# 1-Schematic_BIG_MODULE.net
KiCad netlist of a schematic drawn in EasyEDA
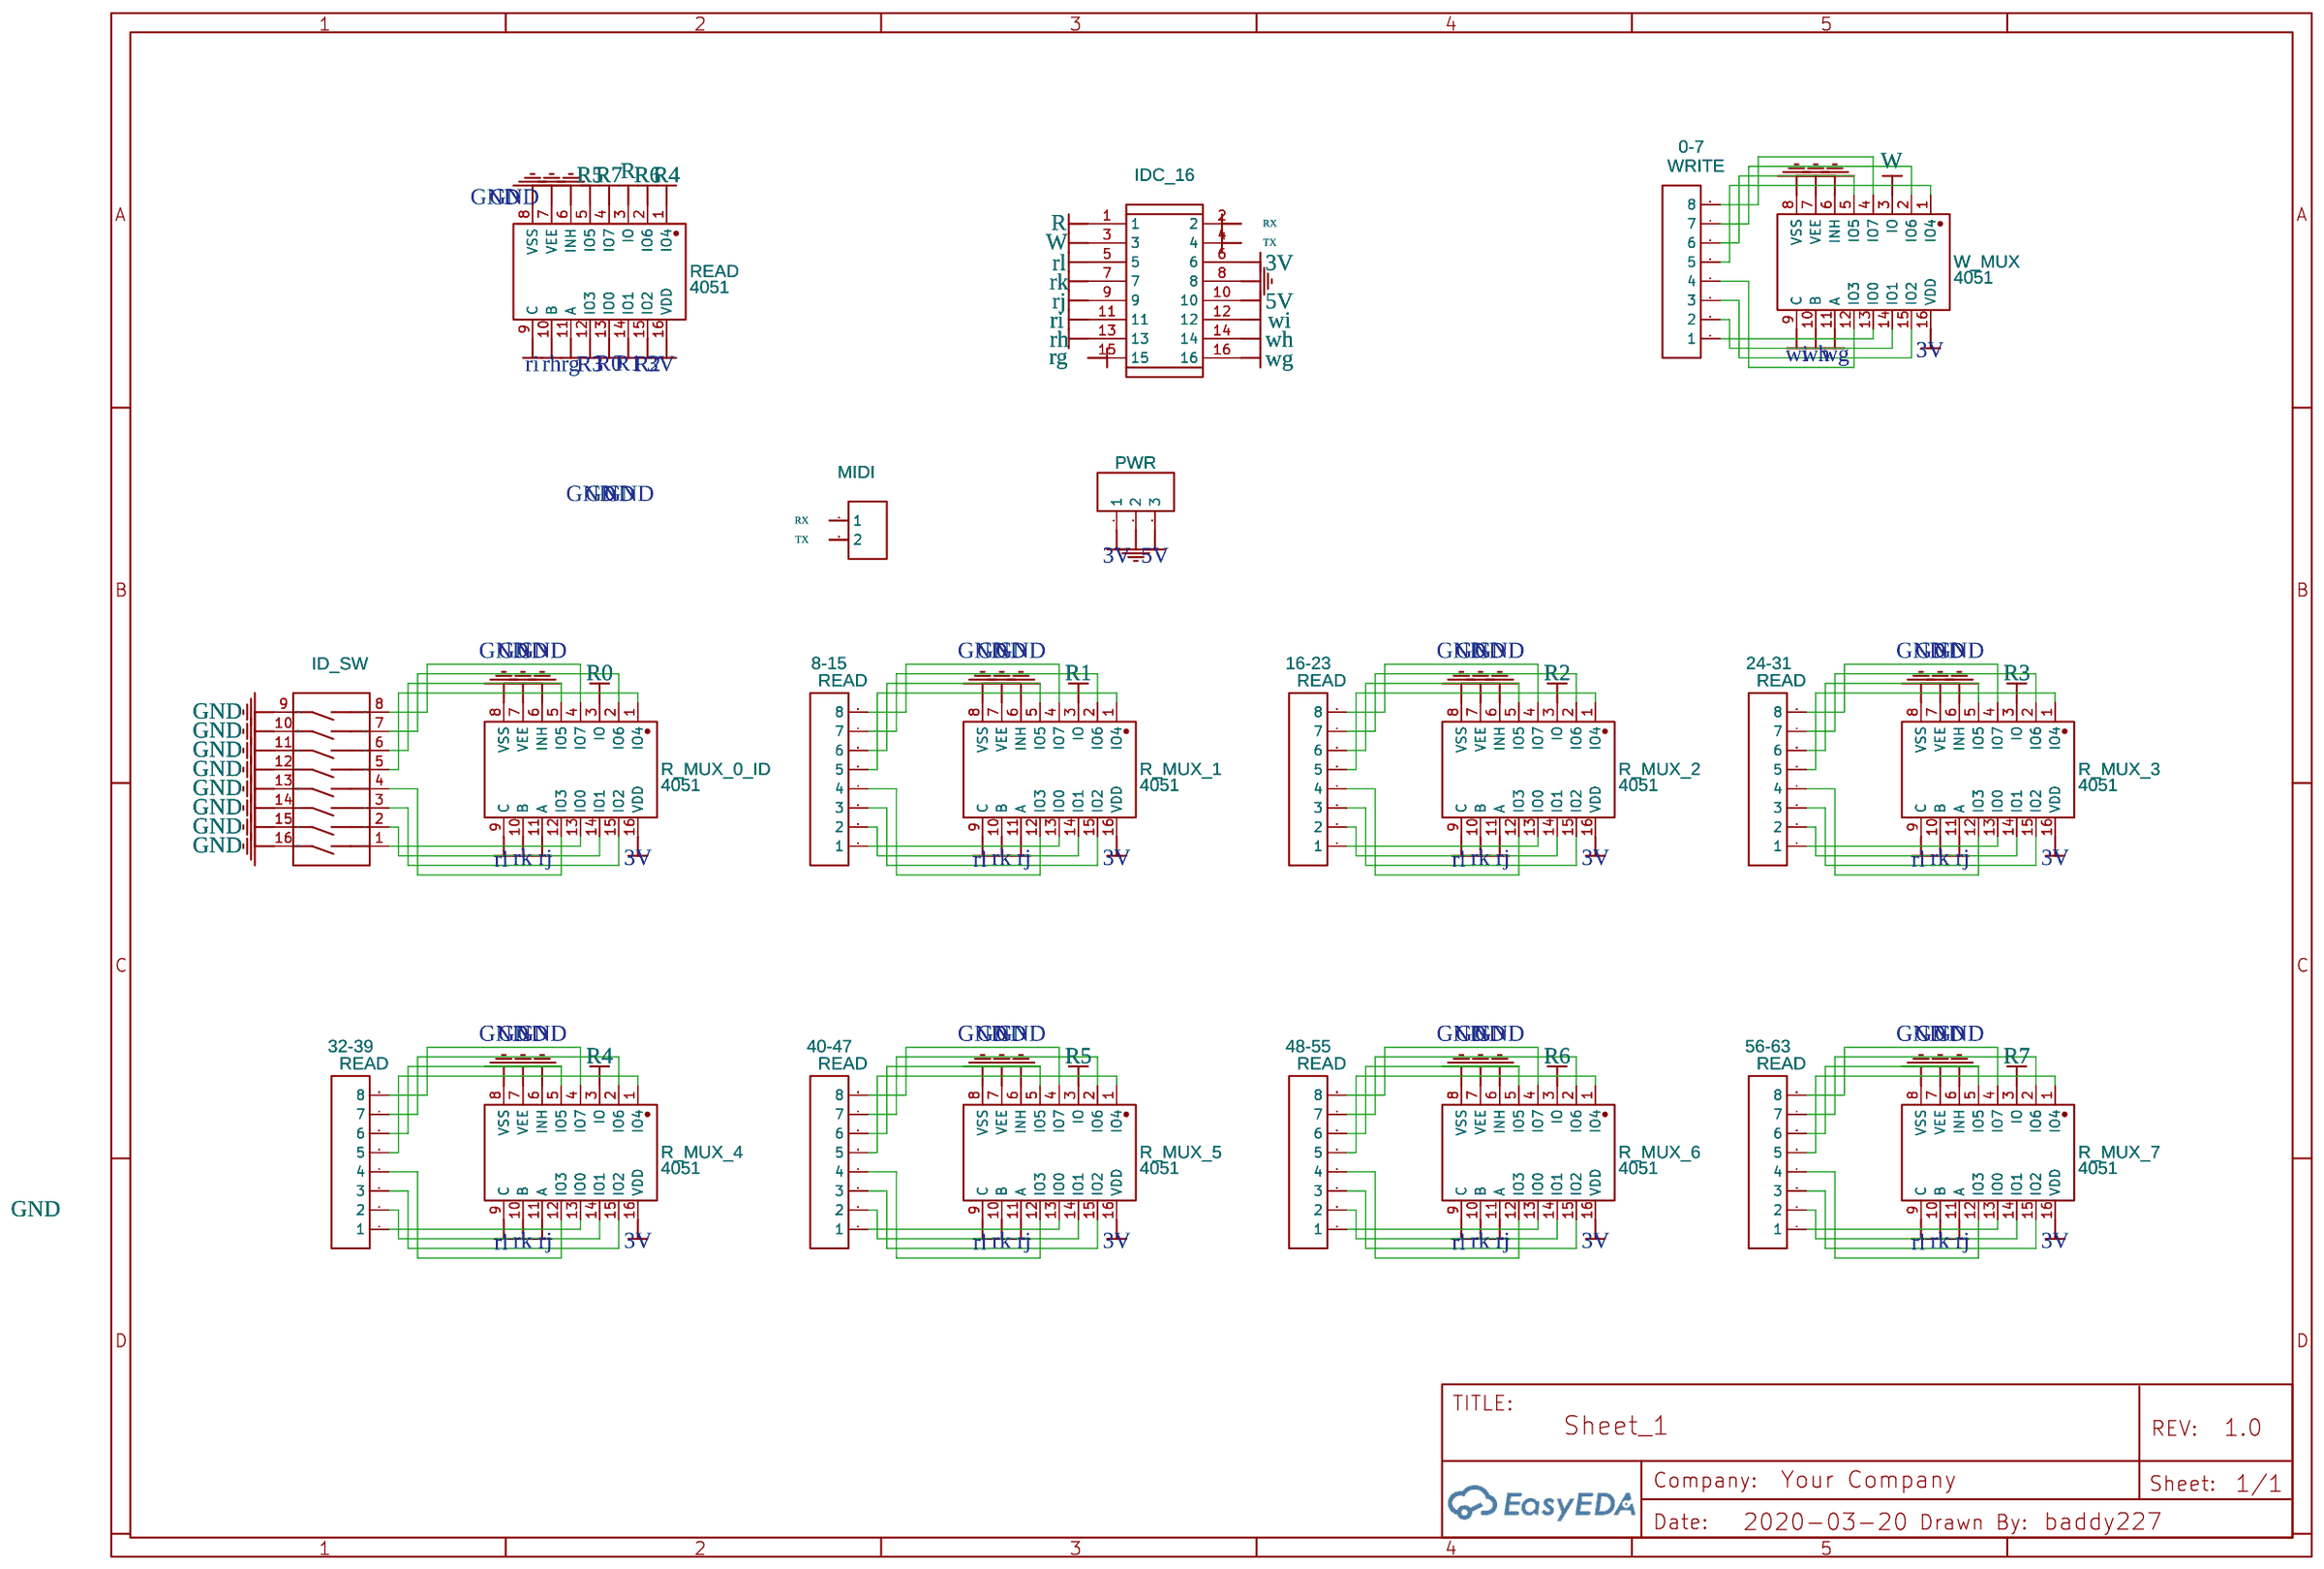
[diagram p0: schematic sheet]

(export (version "E")
  (design (tool "Eeschema 10.0.6"))
  (components
    (comp (ref "8-15")
      (value "READ")
      (fields
        (field (name "BOM_Manufacturer Part") "Female headerHDR1X8-2.54")
        (field (name "BOM_Supplier Part") "C27438")
      )
      (libsource (lib "") (part "Header-Female-2.54_1x8_7"))
    )
    (comp (ref "16-23")
      (value "READ")
      (fields
        (field (name "BOM_Manufacturer Part") "Female headerHDR1X8-2.54")
        (field (name "BOM_Supplier Part") "C27438")
      )
      (libsource (lib "") (part "Header-Female-2.54_1x8_4"))
    )
    (comp (ref "24-31")
      (value "READ")
      (fields
        (field (name "BOM_Manufacturer Part") "Female headerHDR1X8-2.54")
        (field (name "BOM_Supplier Part") "C27438")
      )
      (libsource (lib "") (part "Header-Female-2.54_1x8_3"))
    )
    (comp (ref "32-39")
      (value "READ")
      (fields
        (field (name "BOM_Manufacturer Part") "Female headerHDR1X8-2.54")
        (field (name "BOM_Supplier Part") "C27438")
      )
      (libsource (lib "") (part "Header-Female-2.54_1x8_6"))
    )
    (comp (ref "40-47")
      (value "READ")
      (fields
        (field (name "BOM_Manufacturer Part") "Female headerHDR1X8-2.54")
        (field (name "BOM_Supplier Part") "C27438")
      )
      (libsource (lib "") (part "Header-Female-2.54_1x8"))
    )
    (comp (ref "48-55")
      (value "READ")
      (fields
        (field (name "BOM_Manufacturer Part") "Female headerHDR1X8-2.54")
        (field (name "BOM_Supplier Part") "C27438")
      )
      (libsource (lib "") (part "Header-Female-2.54_1x8_1"))
    )
    (comp (ref "56-63")
      (value "READ")
      (fields
        (field (name "BOM_Manufacturer Part") "Female headerHDR1X8-2.54")
        (field (name "BOM_Supplier Part") "C27438")
      )
      (libsource (lib "") (part "Header-Female-2.54_1x8_2"))
    )
    (comp (ref "IDC_16")
      (value "IDC Box 2X8 2.54MM")
      (fields (field (name "BOM_Supplier Part") "C9142"))
      (libsource (lib "") (part "IDC Box 2X8 2.54MM"))
    )
    (comp (ref "ID_SW")
      (value "DIP switchEI-08")
      (fields (field (name "BOM_Supplier Part") "C90019"))
      (libsource (lib "") (part "DIP switchEI-08"))
    )
    (comp (ref "MIDI")
      (value "HDR-M-2.54_1x2")
      (fields (field (name "BOM_Supplier Part") "C124375"))
      (libsource (lib "") (part "HDR-M-2.54_1x2"))
    )
    (comp (ref "PWR")
      (value "Header-Male-2.54_1x3")
      (fields
        (field (name "BOM_Manufacturer Part") "Header2.54mm 1*3P")
        (field (name "BOM_Supplier Part") "C49257")
      )
      (libsource (lib "") (part "Header-Male-2.54_1x3"))
    )
    (comp (ref "READ")
      (value "4051")
      (fields (field (name "BOM_Manufacturer Part") "CD4051BE") (field (name "BOM_Supplier Part") "C5200"))
      (libsource (lib "") (part "CD4051BE_3"))
    )
    (comp (ref "R_MUX_0_ID")
      (value "4051")
      (fields (field (name "BOM_Manufacturer Part") "CD4051BE") (field (name "BOM_Supplier Part") "C5200"))
      (libsource (lib "") (part "CD4051BE_1"))
    )
    (comp (ref "R_MUX_1")
      (value "4051")
      (fields (field (name "BOM_Manufacturer Part") "CD4051BE") (field (name "BOM_Supplier Part") "C5200"))
      (libsource (lib "") (part "CD4051BE_2"))
    )
    (comp (ref "R_MUX_2")
      (value "4051")
      (fields (field (name "BOM_Manufacturer Part") "CD4051BE") (field (name "BOM_Supplier Part") "C5200"))
      (libsource (lib "") (part "CD4051BE_2"))
    )
    (comp (ref "R_MUX_3")
      (value "4051")
      (fields (field (name "BOM_Manufacturer Part") "CD4051BE") (field (name "BOM_Supplier Part") "C5200"))
      (libsource (lib "") (part "CD4051BE_2"))
    )
    (comp (ref "R_MUX_4")
      (value "4051")
      (fields (field (name "BOM_Manufacturer Part") "CD4051BE") (field (name "BOM_Supplier Part") "C5200"))
      (libsource (lib "") (part "CD4051BE_2"))
    )
    (comp (ref "R_MUX_5")
      (value "4051")
      (fields (field (name "BOM_Manufacturer Part") "CD4051BE") (field (name "BOM_Supplier Part") "C5200"))
      (libsource (lib "") (part "CD4051BE_2"))
    )
    (comp (ref "R_MUX_6")
      (value "4051")
      (fields (field (name "BOM_Manufacturer Part") "CD4051BE") (field (name "BOM_Supplier Part") "C5200"))
      (libsource (lib "") (part "CD4051BE_2"))
    )
    (comp (ref "R_MUX_7")
      (value "4051")
      (fields (field (name "BOM_Manufacturer Part") "CD4051BE") (field (name "BOM_Supplier Part") "C5200"))
      (libsource (lib "") (part "CD4051BE_2"))
    )
    (comp (ref "WRITE")
      (value "0-7")
      (fields
        (field (name "BOM_Manufacturer Part") "Female headerHDR1X8-2.54")
        (field (name "BOM_Supplier Part") "C27438")
      )
      (libsource (lib "") (part "Header-Female-2.54_1x8_5"))
    )
    (comp (ref "W_MUX")
      (value "4051")
      (fields (field (name "BOM_Manufacturer Part") "CD4051BE") (field (name "BOM_Supplier Part") "C5200"))
      (libsource (lib "") (part "CD4051BE"))
    )
  )
  (nets
    (net (code "1") (name "3V") (class "Default")
      (node (ref "IDC_16") (pin "6") (pinfunction "6_6") (pintype "unspecified"))
      (node (ref "PWR") (pin "1") (pinfunction "1_1") (pintype "input"))
      (node (ref "READ") (pin "16") (pinfunction "VDD_16") (pintype "unspecified"))
      (node (ref "R_MUX_0_ID") (pin "16") (pinfunction "VDD_16") (pintype "unspecified"))
      (node (ref "R_MUX_1") (pin "16") (pinfunction "VDD_16") (pintype "unspecified"))
      (node (ref "R_MUX_2") (pin "16") (pinfunction "VDD_16") (pintype "unspecified"))
      (node (ref "R_MUX_3") (pin "16") (pinfunction "VDD_16") (pintype "unspecified"))
      (node (ref "R_MUX_4") (pin "16") (pinfunction "VDD_16") (pintype "unspecified"))
      (node (ref "R_MUX_5") (pin "16") (pinfunction "VDD_16") (pintype "unspecified"))
      (node (ref "R_MUX_6") (pin "16") (pinfunction "VDD_16") (pintype "unspecified"))
      (node (ref "R_MUX_7") (pin "16") (pinfunction "VDD_16") (pintype "unspecified"))
      (node (ref "W_MUX") (pin "16") (pinfunction "VDD_16") (pintype "unspecified"))
    )
    (net (code "2") (name "5V") (class "Default")
      (node (ref "IDC_16") (pin "10") (pinfunction "10_10") (pintype "unspecified"))
      (node (ref "PWR") (pin "3") (pinfunction "3_3") (pintype "input"))
    )
    (net (code "3") (name "GND") (class "Default")
      (node (ref "IDC_16") (pin "8") (pinfunction "8_8") (pintype "unspecified"))
      (node (ref "ID_SW") (pin "10") (pinfunction "10_10") (pintype "unspecified"))
      (node (ref "ID_SW") (pin "11") (pinfunction "11_11") (pintype "unspecified"))
      (node (ref "ID_SW") (pin "12") (pinfunction "12_12") (pintype "unspecified"))
      (node (ref "ID_SW") (pin "13") (pinfunction "13_13") (pintype "unspecified"))
      (node (ref "ID_SW") (pin "14") (pinfunction "14_14") (pintype "unspecified"))
      (node (ref "ID_SW") (pin "15") (pinfunction "15_15") (pintype "unspecified"))
      (node (ref "ID_SW") (pin "16") (pinfunction "16_16") (pintype "unspecified"))
      (node (ref "ID_SW") (pin "9") (pinfunction "9_9") (pintype "unspecified"))
      (node (ref "PWR") (pin "2") (pinfunction "2_2") (pintype "input"))
      (node (ref "READ") (pin "6") (pinfunction "INH_6") (pintype "unspecified"))
      (node (ref "READ") (pin "7") (pinfunction "VEE_7") (pintype "unspecified"))
      (node (ref "READ") (pin "8") (pinfunction "VSS_8") (pintype "unspecified"))
      (node (ref "R_MUX_0_ID") (pin "6") (pinfunction "INH_6") (pintype "unspecified"))
      (node (ref "R_MUX_0_ID") (pin "7") (pinfunction "VEE_7") (pintype "unspecified"))
      (node (ref "R_MUX_0_ID") (pin "8") (pinfunction "VSS_8") (pintype "unspecified"))
      (node (ref "R_MUX_1") (pin "6") (pinfunction "INH_6") (pintype "unspecified"))
      (node (ref "R_MUX_1") (pin "7") (pinfunction "VEE_7") (pintype "unspecified"))
      (node (ref "R_MUX_1") (pin "8") (pinfunction "VSS_8") (pintype "unspecified"))
      (node (ref "R_MUX_2") (pin "6") (pinfunction "INH_6") (pintype "unspecified"))
      (node (ref "R_MUX_2") (pin "7") (pinfunction "VEE_7") (pintype "unspecified"))
      (node (ref "R_MUX_2") (pin "8") (pinfunction "VSS_8") (pintype "unspecified"))
      (node (ref "R_MUX_3") (pin "6") (pinfunction "INH_6") (pintype "unspecified"))
      (node (ref "R_MUX_3") (pin "7") (pinfunction "VEE_7") (pintype "unspecified"))
      (node (ref "R_MUX_3") (pin "8") (pinfunction "VSS_8") (pintype "unspecified"))
      (node (ref "R_MUX_4") (pin "6") (pinfunction "INH_6") (pintype "unspecified"))
      (node (ref "R_MUX_4") (pin "7") (pinfunction "VEE_7") (pintype "unspecified"))
      (node (ref "R_MUX_4") (pin "8") (pinfunction "VSS_8") (pintype "unspecified"))
      (node (ref "R_MUX_5") (pin "6") (pinfunction "INH_6") (pintype "unspecified"))
      (node (ref "R_MUX_5") (pin "7") (pinfunction "VEE_7") (pintype "unspecified"))
      (node (ref "R_MUX_5") (pin "8") (pinfunction "VSS_8") (pintype "unspecified"))
      (node (ref "R_MUX_6") (pin "6") (pinfunction "INH_6") (pintype "unspecified"))
      (node (ref "R_MUX_6") (pin "7") (pinfunction "VEE_7") (pintype "unspecified"))
      (node (ref "R_MUX_6") (pin "8") (pinfunction "VSS_8") (pintype "unspecified"))
      (node (ref "R_MUX_7") (pin "6") (pinfunction "INH_6") (pintype "unspecified"))
      (node (ref "R_MUX_7") (pin "7") (pinfunction "VEE_7") (pintype "unspecified"))
      (node (ref "R_MUX_7") (pin "8") (pinfunction "VSS_8") (pintype "unspecified"))
      (node (ref "W_MUX") (pin "6") (pinfunction "INH_6") (pintype "unspecified"))
      (node (ref "W_MUX") (pin "7") (pinfunction "VEE_7") (pintype "unspecified"))
      (node (ref "W_MUX") (pin "8") (pinfunction "VSS_8") (pintype "unspecified"))
    )
    (net (code "4") (name "Net-(R_MUX_0_ID-IO0)") (class "Default")
      (node (ref "ID_SW") (pin "1") (pinfunction "1_1") (pintype "unspecified"))
      (node (ref "R_MUX_0_ID") (pin "13") (pinfunction "IO0_13") (pintype "unspecified"))
    )
    (net (code "5") (name "Net-(R_MUX_0_ID-IO1)") (class "Default")
      (node (ref "ID_SW") (pin "2") (pinfunction "2_2") (pintype "unspecified"))
      (node (ref "R_MUX_0_ID") (pin "14") (pinfunction "IO1_14") (pintype "unspecified"))
    )
    (net (code "6") (name "Net-(R_MUX_0_ID-IO2)") (class "Default")
      (node (ref "ID_SW") (pin "3") (pinfunction "3_3") (pintype "unspecified"))
      (node (ref "R_MUX_0_ID") (pin "15") (pinfunction "IO2_15") (pintype "unspecified"))
    )
    (net (code "7") (name "Net-(R_MUX_0_ID-IO3)") (class "Default")
      (node (ref "ID_SW") (pin "4") (pinfunction "4_4") (pintype "unspecified"))
      (node (ref "R_MUX_0_ID") (pin "12") (pinfunction "IO3_12") (pintype "unspecified"))
    )
    (net (code "8") (name "Net-(R_MUX_0_ID-IO4)") (class "Default")
      (node (ref "ID_SW") (pin "5") (pinfunction "5_5") (pintype "unspecified"))
      (node (ref "R_MUX_0_ID") (pin "1") (pinfunction "IO4_1") (pintype "unspecified"))
    )
    (net (code "9") (name "Net-(R_MUX_0_ID-IO5)") (class "Default")
      (node (ref "ID_SW") (pin "6") (pinfunction "6_6") (pintype "unspecified"))
      (node (ref "R_MUX_0_ID") (pin "5") (pinfunction "IO5_5") (pintype "unspecified"))
    )
    (net (code "10") (name "Net-(R_MUX_0_ID-IO6)") (class "Default")
      (node (ref "ID_SW") (pin "7") (pinfunction "7_7") (pintype "unspecified"))
      (node (ref "R_MUX_0_ID") (pin "2") (pinfunction "IO6_2") (pintype "unspecified"))
    )
    (net (code "11") (name "Net-(R_MUX_0_ID-IO7)") (class "Default")
      (node (ref "ID_SW") (pin "8") (pinfunction "8_8") (pintype "unspecified"))
      (node (ref "R_MUX_0_ID") (pin "4") (pinfunction "IO7_4") (pintype "unspecified"))
    )
    (net (code "12") (name "Net-(R_MUX_1-IO0)") (class "Default")
      (node (ref "8-15") (pin "1") (pinfunction "1_1") (pintype "input"))
      (node (ref "R_MUX_1") (pin "13") (pinfunction "IO0_13") (pintype "unspecified"))
    )
    (net (code "13") (name "Net-(R_MUX_1-IO1)") (class "Default")
      (node (ref "8-15") (pin "2") (pinfunction "2_2") (pintype "input"))
      (node (ref "R_MUX_1") (pin "14") (pinfunction "IO1_14") (pintype "unspecified"))
    )
    (net (code "14") (name "Net-(R_MUX_1-IO2)") (class "Default")
      (node (ref "8-15") (pin "3") (pinfunction "3_3") (pintype "input"))
      (node (ref "R_MUX_1") (pin "15") (pinfunction "IO2_15") (pintype "unspecified"))
    )
    (net (code "15") (name "Net-(R_MUX_1-IO3)") (class "Default")
      (node (ref "8-15") (pin "4") (pinfunction "4_4") (pintype "input"))
      (node (ref "R_MUX_1") (pin "12") (pinfunction "IO3_12") (pintype "unspecified"))
    )
    (net (code "16") (name "Net-(R_MUX_1-IO4)") (class "Default")
      (node (ref "8-15") (pin "5") (pinfunction "5_5") (pintype "input"))
      (node (ref "R_MUX_1") (pin "1") (pinfunction "IO4_1") (pintype "unspecified"))
    )
    (net (code "17") (name "Net-(R_MUX_1-IO5)") (class "Default")
      (node (ref "8-15") (pin "6") (pinfunction "6_6") (pintype "input"))
      (node (ref "R_MUX_1") (pin "5") (pinfunction "IO5_5") (pintype "unspecified"))
    )
    (net (code "18") (name "Net-(R_MUX_1-IO6)") (class "Default")
      (node (ref "8-15") (pin "7") (pinfunction "7_7") (pintype "input"))
      (node (ref "R_MUX_1") (pin "2") (pinfunction "IO6_2") (pintype "unspecified"))
    )
    (net (code "19") (name "Net-(R_MUX_1-IO7)") (class "Default")
      (node (ref "8-15") (pin "8") (pinfunction "8_8") (pintype "input"))
      (node (ref "R_MUX_1") (pin "4") (pinfunction "IO7_4") (pintype "unspecified"))
    )
    (net (code "20") (name "Net-(R_MUX_2-IO0)") (class "Default")
      (node (ref "16-23") (pin "1") (pinfunction "1_1") (pintype "input"))
      (node (ref "R_MUX_2") (pin "13") (pinfunction "IO0_13") (pintype "unspecified"))
    )
    (net (code "21") (name "Net-(R_MUX_2-IO1)") (class "Default")
      (node (ref "16-23") (pin "2") (pinfunction "2_2") (pintype "input"))
      (node (ref "R_MUX_2") (pin "14") (pinfunction "IO1_14") (pintype "unspecified"))
    )
    (net (code "22") (name "Net-(R_MUX_2-IO2)") (class "Default")
      (node (ref "16-23") (pin "3") (pinfunction "3_3") (pintype "input"))
      (node (ref "R_MUX_2") (pin "15") (pinfunction "IO2_15") (pintype "unspecified"))
    )
    (net (code "23") (name "Net-(R_MUX_2-IO3)") (class "Default")
      (node (ref "16-23") (pin "4") (pinfunction "4_4") (pintype "input"))
      (node (ref "R_MUX_2") (pin "12") (pinfunction "IO3_12") (pintype "unspecified"))
    )
    (net (code "24") (name "Net-(R_MUX_2-IO4)") (class "Default")
      (node (ref "16-23") (pin "5") (pinfunction "5_5") (pintype "input"))
      (node (ref "R_MUX_2") (pin "1") (pinfunction "IO4_1") (pintype "unspecified"))
    )
    (net (code "25") (name "Net-(R_MUX_2-IO5)") (class "Default")
      (node (ref "16-23") (pin "6") (pinfunction "6_6") (pintype "input"))
      (node (ref "R_MUX_2") (pin "5") (pinfunction "IO5_5") (pintype "unspecified"))
    )
    (net (code "26") (name "Net-(R_MUX_2-IO6)") (class "Default")
      (node (ref "16-23") (pin "7") (pinfunction "7_7") (pintype "input"))
      (node (ref "R_MUX_2") (pin "2") (pinfunction "IO6_2") (pintype "unspecified"))
    )
    (net (code "27") (name "Net-(R_MUX_2-IO7)") (class "Default")
      (node (ref "16-23") (pin "8") (pinfunction "8_8") (pintype "input"))
      (node (ref "R_MUX_2") (pin "4") (pinfunction "IO7_4") (pintype "unspecified"))
    )
    (net (code "28") (name "Net-(R_MUX_3-IO0)") (class "Default")
      (node (ref "24-31") (pin "1") (pinfunction "1_1") (pintype "input"))
      (node (ref "R_MUX_3") (pin "13") (pinfunction "IO0_13") (pintype "unspecified"))
    )
    (net (code "29") (name "Net-(R_MUX_3-IO1)") (class "Default")
      (node (ref "24-31") (pin "2") (pinfunction "2_2") (pintype "input"))
      (node (ref "R_MUX_3") (pin "14") (pinfunction "IO1_14") (pintype "unspecified"))
    )
    (net (code "30") (name "Net-(R_MUX_3-IO2)") (class "Default")
      (node (ref "24-31") (pin "3") (pinfunction "3_3") (pintype "input"))
      (node (ref "R_MUX_3") (pin "15") (pinfunction "IO2_15") (pintype "unspecified"))
    )
    (net (code "31") (name "Net-(R_MUX_3-IO3)") (class "Default")
      (node (ref "24-31") (pin "4") (pinfunction "4_4") (pintype "input"))
      (node (ref "R_MUX_3") (pin "12") (pinfunction "IO3_12") (pintype "unspecified"))
    )
    (net (code "32") (name "Net-(R_MUX_3-IO4)") (class "Default")
      (node (ref "24-31") (pin "5") (pinfunction "5_5") (pintype "input"))
      (node (ref "R_MUX_3") (pin "1") (pinfunction "IO4_1") (pintype "unspecified"))
    )
    (net (code "33") (name "Net-(R_MUX_3-IO5)") (class "Default")
      (node (ref "24-31") (pin "6") (pinfunction "6_6") (pintype "input"))
      (node (ref "R_MUX_3") (pin "5") (pinfunction "IO5_5") (pintype "unspecified"))
    )
    (net (code "34") (name "Net-(R_MUX_3-IO6)") (class "Default")
      (node (ref "24-31") (pin "7") (pinfunction "7_7") (pintype "input"))
      (node (ref "R_MUX_3") (pin "2") (pinfunction "IO6_2") (pintype "unspecified"))
    )
    (net (code "35") (name "Net-(R_MUX_3-IO7)") (class "Default")
      (node (ref "24-31") (pin "8") (pinfunction "8_8") (pintype "input"))
      (node (ref "R_MUX_3") (pin "4") (pinfunction "IO7_4") (pintype "unspecified"))
    )
    (net (code "36") (name "Net-(R_MUX_4-IO0)") (class "Default")
      (node (ref "32-39") (pin "1") (pinfunction "1_1") (pintype "input"))
      (node (ref "R_MUX_4") (pin "13") (pinfunction "IO0_13") (pintype "unspecified"))
    )
    (net (code "37") (name "Net-(R_MUX_4-IO1)") (class "Default")
      (node (ref "32-39") (pin "2") (pinfunction "2_2") (pintype "input"))
      (node (ref "R_MUX_4") (pin "14") (pinfunction "IO1_14") (pintype "unspecified"))
    )
    (net (code "38") (name "Net-(R_MUX_4-IO2)") (class "Default")
      (node (ref "32-39") (pin "3") (pinfunction "3_3") (pintype "input"))
      (node (ref "R_MUX_4") (pin "15") (pinfunction "IO2_15") (pintype "unspecified"))
    )
    (net (code "39") (name "Net-(R_MUX_4-IO3)") (class "Default")
      (node (ref "32-39") (pin "4") (pinfunction "4_4") (pintype "input"))
      (node (ref "R_MUX_4") (pin "12") (pinfunction "IO3_12") (pintype "unspecified"))
    )
    (net (code "40") (name "Net-(R_MUX_4-IO4)") (class "Default")
      (node (ref "32-39") (pin "5") (pinfunction "5_5") (pintype "input"))
      (node (ref "R_MUX_4") (pin "1") (pinfunction "IO4_1") (pintype "unspecified"))
    )
    (net (code "41") (name "Net-(R_MUX_4-IO5)") (class "Default")
      (node (ref "32-39") (pin "6") (pinfunction "6_6") (pintype "input"))
      (node (ref "R_MUX_4") (pin "5") (pinfunction "IO5_5") (pintype "unspecified"))
    )
    (net (code "42") (name "Net-(R_MUX_4-IO6)") (class "Default")
      (node (ref "32-39") (pin "7") (pinfunction "7_7") (pintype "input"))
      (node (ref "R_MUX_4") (pin "2") (pinfunction "IO6_2") (pintype "unspecified"))
    )
    (net (code "43") (name "Net-(R_MUX_4-IO7)") (class "Default")
      (node (ref "32-39") (pin "8") (pinfunction "8_8") (pintype "input"))
      (node (ref "R_MUX_4") (pin "4") (pinfunction "IO7_4") (pintype "unspecified"))
    )
    (net (code "44") (name "Net-(R_MUX_5-IO0)") (class "Default")
      (node (ref "40-47") (pin "1") (pinfunction "1_1") (pintype "input"))
      (node (ref "R_MUX_5") (pin "13") (pinfunction "IO0_13") (pintype "unspecified"))
    )
    (net (code "45") (name "Net-(R_MUX_5-IO1)") (class "Default")
      (node (ref "40-47") (pin "2") (pinfunction "2_2") (pintype "input"))
      (node (ref "R_MUX_5") (pin "14") (pinfunction "IO1_14") (pintype "unspecified"))
    )
    (net (code "46") (name "Net-(R_MUX_5-IO2)") (class "Default")
      (node (ref "40-47") (pin "3") (pinfunction "3_3") (pintype "input"))
      (node (ref "R_MUX_5") (pin "15") (pinfunction "IO2_15") (pintype "unspecified"))
    )
    (net (code "47") (name "Net-(R_MUX_5-IO3)") (class "Default")
      (node (ref "40-47") (pin "4") (pinfunction "4_4") (pintype "input"))
      (node (ref "R_MUX_5") (pin "12") (pinfunction "IO3_12") (pintype "unspecified"))
    )
    (net (code "48") (name "Net-(R_MUX_5-IO4)") (class "Default")
      (node (ref "40-47") (pin "5") (pinfunction "5_5") (pintype "input"))
      (node (ref "R_MUX_5") (pin "1") (pinfunction "IO4_1") (pintype "unspecified"))
    )
    (net (code "49") (name "Net-(R_MUX_5-IO5)") (class "Default")
      (node (ref "40-47") (pin "6") (pinfunction "6_6") (pintype "input"))
      (node (ref "R_MUX_5") (pin "5") (pinfunction "IO5_5") (pintype "unspecified"))
    )
    (net (code "50") (name "Net-(R_MUX_5-IO6)") (class "Default")
      (node (ref "40-47") (pin "7") (pinfunction "7_7") (pintype "input"))
      (node (ref "R_MUX_5") (pin "2") (pinfunction "IO6_2") (pintype "unspecified"))
    )
    (net (code "51") (name "Net-(R_MUX_5-IO7)") (class "Default")
      (node (ref "40-47") (pin "8") (pinfunction "8_8") (pintype "input"))
      (node (ref "R_MUX_5") (pin "4") (pinfunction "IO7_4") (pintype "unspecified"))
    )
    (net (code "52") (name "Net-(R_MUX_6-IO0)") (class "Default")
      (node (ref "48-55") (pin "1") (pinfunction "1_1") (pintype "input"))
      (node (ref "R_MUX_6") (pin "13") (pinfunction "IO0_13") (pintype "unspecified"))
    )
    (net (code "53") (name "Net-(R_MUX_6-IO1)") (class "Default")
      (node (ref "48-55") (pin "2") (pinfunction "2_2") (pintype "input"))
      (node (ref "R_MUX_6") (pin "14") (pinfunction "IO1_14") (pintype "unspecified"))
    )
    (net (code "54") (name "Net-(R_MUX_6-IO2)") (class "Default")
      (node (ref "48-55") (pin "3") (pinfunction "3_3") (pintype "input"))
      (node (ref "R_MUX_6") (pin "15") (pinfunction "IO2_15") (pintype "unspecified"))
    )
    (net (code "55") (name "Net-(R_MUX_6-IO3)") (class "Default")
      (node (ref "48-55") (pin "4") (pinfunction "4_4") (pintype "input"))
      (node (ref "R_MUX_6") (pin "12") (pinfunction "IO3_12") (pintype "unspecified"))
    )
    (net (code "56") (name "Net-(R_MUX_6-IO4)") (class "Default")
      (node (ref "48-55") (pin "5") (pinfunction "5_5") (pintype "input"))
      (node (ref "R_MUX_6") (pin "1") (pinfunction "IO4_1") (pintype "unspecified"))
    )
    (net (code "57") (name "Net-(R_MUX_6-IO5)") (class "Default")
      (node (ref "48-55") (pin "6") (pinfunction "6_6") (pintype "input"))
      (node (ref "R_MUX_6") (pin "5") (pinfunction "IO5_5") (pintype "unspecified"))
    )
    (net (code "58") (name "Net-(R_MUX_6-IO6)") (class "Default")
      (node (ref "48-55") (pin "7") (pinfunction "7_7") (pintype "input"))
      (node (ref "R_MUX_6") (pin "2") (pinfunction "IO6_2") (pintype "unspecified"))
    )
    (net (code "59") (name "Net-(R_MUX_6-IO7)") (class "Default")
      (node (ref "48-55") (pin "8") (pinfunction "8_8") (pintype "input"))
      (node (ref "R_MUX_6") (pin "4") (pinfunction "IO7_4") (pintype "unspecified"))
    )
    (net (code "60") (name "Net-(R_MUX_7-IO0)") (class "Default")
      (node (ref "56-63") (pin "1") (pinfunction "1_1") (pintype "input"))
      (node (ref "R_MUX_7") (pin "13") (pinfunction "IO0_13") (pintype "unspecified"))
    )
    (net (code "61") (name "Net-(R_MUX_7-IO1)") (class "Default")
      (node (ref "56-63") (pin "2") (pinfunction "2_2") (pintype "input"))
      (node (ref "R_MUX_7") (pin "14") (pinfunction "IO1_14") (pintype "unspecified"))
    )
    (net (code "62") (name "Net-(R_MUX_7-IO2)") (class "Default")
      (node (ref "56-63") (pin "3") (pinfunction "3_3") (pintype "input"))
      (node (ref "R_MUX_7") (pin "15") (pinfunction "IO2_15") (pintype "unspecified"))
    )
    (net (code "63") (name "Net-(R_MUX_7-IO3)") (class "Default")
      (node (ref "56-63") (pin "4") (pinfunction "4_4") (pintype "input"))
      (node (ref "R_MUX_7") (pin "12") (pinfunction "IO3_12") (pintype "unspecified"))
    )
    (net (code "64") (name "Net-(R_MUX_7-IO4)") (class "Default")
      (node (ref "56-63") (pin "5") (pinfunction "5_5") (pintype "input"))
      (node (ref "R_MUX_7") (pin "1") (pinfunction "IO4_1") (pintype "unspecified"))
    )
    (net (code "65") (name "Net-(R_MUX_7-IO5)") (class "Default")
      (node (ref "56-63") (pin "6") (pinfunction "6_6") (pintype "input"))
      (node (ref "R_MUX_7") (pin "5") (pinfunction "IO5_5") (pintype "unspecified"))
    )
    (net (code "66") (name "Net-(R_MUX_7-IO6)") (class "Default")
      (node (ref "56-63") (pin "7") (pinfunction "7_7") (pintype "input"))
      (node (ref "R_MUX_7") (pin "2") (pinfunction "IO6_2") (pintype "unspecified"))
    )
    (net (code "67") (name "Net-(R_MUX_7-IO7)") (class "Default")
      (node (ref "56-63") (pin "8") (pinfunction "8_8") (pintype "input"))
      (node (ref "R_MUX_7") (pin "4") (pinfunction "IO7_4") (pintype "unspecified"))
    )
    (net (code "68") (name "Net-(W_MUX-IO0)") (class "Default")
      (node (ref "WRITE") (pin "1") (pinfunction "1_1") (pintype "input"))
      (node (ref "W_MUX") (pin "13") (pinfunction "IO0_13") (pintype "unspecified"))
    )
    (net (code "69") (name "Net-(W_MUX-IO1)") (class "Default")
      (node (ref "WRITE") (pin "2") (pinfunction "2_2") (pintype "input"))
      (node (ref "W_MUX") (pin "14") (pinfunction "IO1_14") (pintype "unspecified"))
    )
    (net (code "70") (name "Net-(W_MUX-IO2)") (class "Default")
      (node (ref "WRITE") (pin "3") (pinfunction "3_3") (pintype "input"))
      (node (ref "W_MUX") (pin "15") (pinfunction "IO2_15") (pintype "unspecified"))
    )
    (net (code "71") (name "Net-(W_MUX-IO3)") (class "Default")
      (node (ref "WRITE") (pin "4") (pinfunction "4_4") (pintype "input"))
      (node (ref "W_MUX") (pin "12") (pinfunction "IO3_12") (pintype "unspecified"))
    )
    (net (code "72") (name "Net-(W_MUX-IO4)") (class "Default")
      (node (ref "WRITE") (pin "5") (pinfunction "5_5") (pintype "input"))
      (node (ref "W_MUX") (pin "1") (pinfunction "IO4_1") (pintype "unspecified"))
    )
    (net (code "73") (name "Net-(W_MUX-IO5)") (class "Default")
      (node (ref "WRITE") (pin "6") (pinfunction "6_6") (pintype "input"))
      (node (ref "W_MUX") (pin "5") (pinfunction "IO5_5") (pintype "unspecified"))
    )
    (net (code "74") (name "Net-(W_MUX-IO6)") (class "Default")
      (node (ref "WRITE") (pin "7") (pinfunction "7_7") (pintype "input"))
      (node (ref "W_MUX") (pin "2") (pinfunction "IO6_2") (pintype "unspecified"))
    )
    (net (code "75") (name "Net-(W_MUX-IO7)") (class "Default")
      (node (ref "WRITE") (pin "8") (pinfunction "8_8") (pintype "input"))
      (node (ref "W_MUX") (pin "4") (pinfunction "IO7_4") (pintype "unspecified"))
    )
    (net (code "76") (name "R") (class "Default")
      (node (ref "IDC_16") (pin "1") (pinfunction "1_1") (pintype "unspecified"))
      (node (ref "READ") (pin "3") (pinfunction "IO_3") (pintype "unspecified"))
    )
    (net (code "77") (name "R0") (class "Default")
      (node (ref "READ") (pin "13") (pinfunction "IO0_13") (pintype "unspecified"))
      (node (ref "R_MUX_0_ID") (pin "3") (pinfunction "IO_3") (pintype "unspecified"))
    )
    (net (code "78") (name "R1") (class "Default")
      (node (ref "READ") (pin "14") (pinfunction "IO1_14") (pintype "unspecified"))
      (node (ref "R_MUX_1") (pin "3") (pinfunction "IO_3") (pintype "unspecified"))
    )
    (net (code "79") (name "R2") (class "Default")
      (node (ref "READ") (pin "15") (pinfunction "IO2_15") (pintype "unspecified"))
      (node (ref "R_MUX_2") (pin "3") (pinfunction "IO_3") (pintype "unspecified"))
    )
    (net (code "80") (name "R3") (class "Default")
      (node (ref "READ") (pin "12") (pinfunction "IO3_12") (pintype "unspecified"))
      (node (ref "R_MUX_3") (pin "3") (pinfunction "IO_3") (pintype "unspecified"))
    )
    (net (code "81") (name "R4") (class "Default")
      (node (ref "READ") (pin "1") (pinfunction "IO4_1") (pintype "unspecified"))
      (node (ref "R_MUX_4") (pin "3") (pinfunction "IO_3") (pintype "unspecified"))
    )
    (net (code "82") (name "R5") (class "Default")
      (node (ref "READ") (pin "5") (pinfunction "IO5_5") (pintype "unspecified"))
      (node (ref "R_MUX_5") (pin "3") (pinfunction "IO_3") (pintype "unspecified"))
    )
    (net (code "83") (name "R6") (class "Default")
      (node (ref "READ") (pin "2") (pinfunction "IO6_2") (pintype "unspecified"))
      (node (ref "R_MUX_6") (pin "3") (pinfunction "IO_3") (pintype "unspecified"))
    )
    (net (code "84") (name "R7") (class "Default")
      (node (ref "READ") (pin "4") (pinfunction "IO7_4") (pintype "unspecified"))
      (node (ref "R_MUX_7") (pin "3") (pinfunction "IO_3") (pintype "unspecified"))
    )
    (net (code "85") (name "RX") (class "Default")
      (node (ref "IDC_16") (pin "2") (pinfunction "2_2") (pintype "unspecified"))
      (node (ref "MIDI") (pin "1") (pinfunction "1_1") (pintype "unspecified"))
    )
    (net (code "86") (name "TX") (class "Default")
      (node (ref "IDC_16") (pin "4") (pinfunction "4_4") (pintype "unspecified"))
      (node (ref "MIDI") (pin "2") (pinfunction "2_2") (pintype "unspecified"))
    )
    (net (code "87") (name "W") (class "Default")
      (node (ref "IDC_16") (pin "3") (pinfunction "3_3") (pintype "unspecified"))
      (node (ref "W_MUX") (pin "3") (pinfunction "IO_3") (pintype "unspecified"))
    )
    (net (code "88") (name "rg") (class "Default")
      (node (ref "IDC_16") (pin "15") (pinfunction "15_15") (pintype "unspecified"))
      (node (ref "READ") (pin "11") (pinfunction "A_11") (pintype "unspecified"))
    )
    (net (code "89") (name "rh") (class "Default")
      (node (ref "IDC_16") (pin "13") (pinfunction "13_13") (pintype "unspecified"))
      (node (ref "READ") (pin "10") (pinfunction "B_10") (pintype "unspecified"))
    )
    (net (code "90") (name "ri") (class "Default")
      (node (ref "IDC_16") (pin "11") (pinfunction "11_11") (pintype "unspecified"))
      (node (ref "READ") (pin "9") (pinfunction "C_9") (pintype "unspecified"))
    )
    (net (code "91") (name "rj") (class "Default")
      (node (ref "IDC_16") (pin "9") (pinfunction "9_9") (pintype "unspecified"))
      (node (ref "R_MUX_0_ID") (pin "11") (pinfunction "A_11") (pintype "unspecified"))
      (node (ref "R_MUX_1") (pin "11") (pinfunction "A_11") (pintype "unspecified"))
      (node (ref "R_MUX_2") (pin "11") (pinfunction "A_11") (pintype "unspecified"))
      (node (ref "R_MUX_3") (pin "11") (pinfunction "A_11") (pintype "unspecified"))
      (node (ref "R_MUX_4") (pin "11") (pinfunction "A_11") (pintype "unspecified"))
      (node (ref "R_MUX_5") (pin "11") (pinfunction "A_11") (pintype "unspecified"))
      (node (ref "R_MUX_6") (pin "11") (pinfunction "A_11") (pintype "unspecified"))
      (node (ref "R_MUX_7") (pin "11") (pinfunction "A_11") (pintype "unspecified"))
    )
    (net (code "92") (name "rk") (class "Default")
      (node (ref "IDC_16") (pin "7") (pinfunction "7_7") (pintype "unspecified"))
      (node (ref "R_MUX_0_ID") (pin "10") (pinfunction "B_10") (pintype "unspecified"))
      (node (ref "R_MUX_1") (pin "10") (pinfunction "B_10") (pintype "unspecified"))
      (node (ref "R_MUX_2") (pin "10") (pinfunction "B_10") (pintype "unspecified"))
      (node (ref "R_MUX_3") (pin "10") (pinfunction "B_10") (pintype "unspecified"))
      (node (ref "R_MUX_4") (pin "10") (pinfunction "B_10") (pintype "unspecified"))
      (node (ref "R_MUX_5") (pin "10") (pinfunction "B_10") (pintype "unspecified"))
      (node (ref "R_MUX_6") (pin "10") (pinfunction "B_10") (pintype "unspecified"))
      (node (ref "R_MUX_7") (pin "10") (pinfunction "B_10") (pintype "unspecified"))
    )
    (net (code "93") (name "rl") (class "Default")
      (node (ref "IDC_16") (pin "5") (pinfunction "5_5") (pintype "unspecified"))
      (node (ref "R_MUX_0_ID") (pin "9") (pinfunction "C_9") (pintype "unspecified"))
      (node (ref "R_MUX_1") (pin "9") (pinfunction "C_9") (pintype "unspecified"))
      (node (ref "R_MUX_2") (pin "9") (pinfunction "C_9") (pintype "unspecified"))
      (node (ref "R_MUX_3") (pin "9") (pinfunction "C_9") (pintype "unspecified"))
      (node (ref "R_MUX_4") (pin "9") (pinfunction "C_9") (pintype "unspecified"))
      (node (ref "R_MUX_5") (pin "9") (pinfunction "C_9") (pintype "unspecified"))
      (node (ref "R_MUX_6") (pin "9") (pinfunction "C_9") (pintype "unspecified"))
      (node (ref "R_MUX_7") (pin "9") (pinfunction "C_9") (pintype "unspecified"))
    )
    (net (code "94") (name "wg") (class "Default")
      (node (ref "IDC_16") (pin "16") (pinfunction "16_16") (pintype "unspecified"))
      (node (ref "W_MUX") (pin "11") (pinfunction "A_11") (pintype "unspecified"))
    )
    (net (code "95") (name "wh") (class "Default")
      (node (ref "IDC_16") (pin "14") (pinfunction "14_14") (pintype "unspecified"))
      (node (ref "W_MUX") (pin "10") (pinfunction "B_10") (pintype "unspecified"))
    )
    (net (code "96") (name "wi") (class "Default")
      (node (ref "IDC_16") (pin "12") (pinfunction "12_12") (pintype "unspecified"))
      (node (ref "W_MUX") (pin "9") (pinfunction "C_9") (pintype "unspecified"))
    )
  )
)
